# SimpleBattCharger.net
KiCad netlist of a schematic drawn in EAGLE
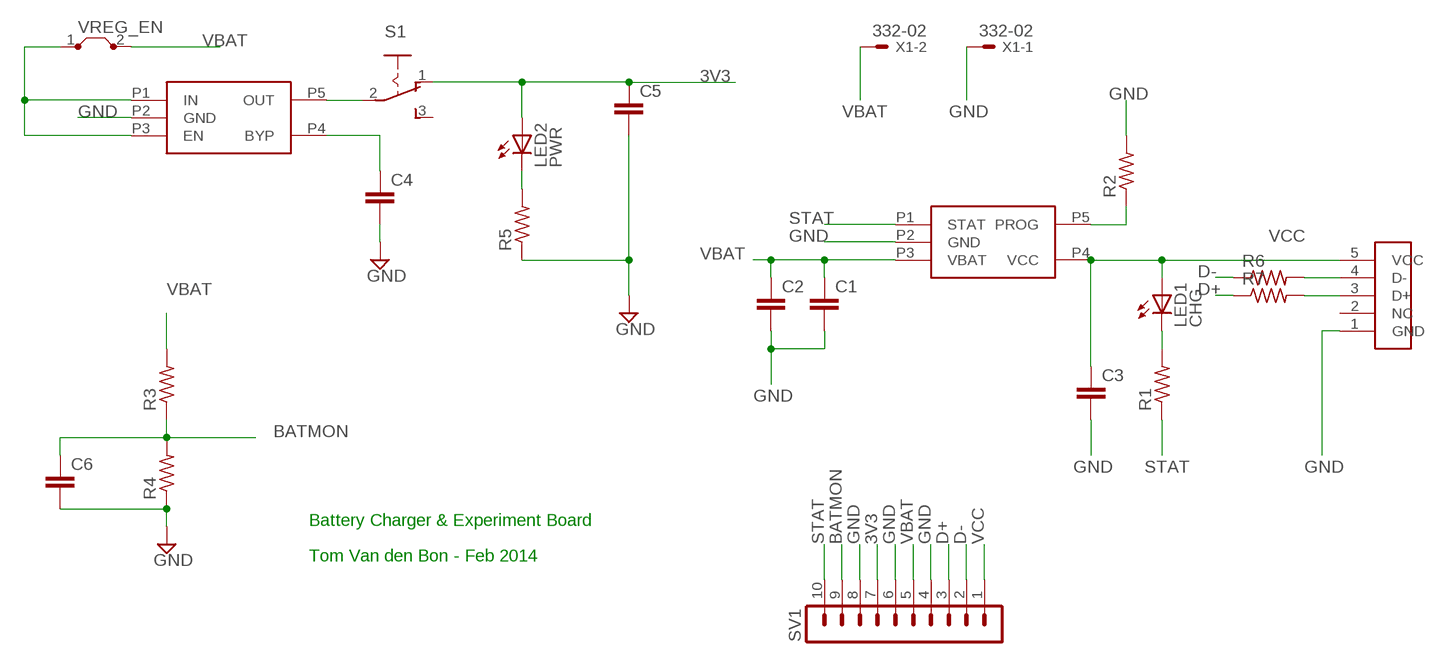
[diagram p0: schematic, sheet 1]

(export (version "E")
  (design (tool "Eeschema 10.0.6"))
  (components
    (comp (ref "C1")
      (value "C-EUC0603K")
      (footprint "eagle-import:C0603K")
      (libsource (lib "eagle-import") (part "C-EUC0603K"))
    )
    (comp (ref "C2")
      (value "C-EUC0603K")
      (footprint "eagle-import:C0603K")
      (libsource (lib "eagle-import") (part "C-EUC0603K"))
    )
    (comp (ref "C3")
      (value "C-EUC0603K")
      (footprint "eagle-import:C0603K")
      (libsource (lib "eagle-import") (part "C-EUC0603K"))
    )
    (comp (ref "C4")
      (value "C-EUC0603")
      (footprint "eagle-import:C0603")
      (libsource (lib "eagle-import") (part "C-EUC0603"))
    )
    (comp (ref "C5")
      (value "C-EUC3225")
      (footprint "eagle-import:C3225")
      (libsource (lib "eagle-import") (part "C-EUC3225"))
    )
    (comp (ref "C6")
      (value "C-EUC0603")
      (footprint "eagle-import:C0603")
      (libsource (lib "eagle-import") (part "C-EUC0603"))
    )
    (comp (ref "LED1")
      (value "CHG")
      (footprint "eagle-import:SML0603")
      (libsource (lib "eagle-import") (part "LEDSML0603"))
    )
    (comp (ref "LED2")
      (value "PWR")
      (footprint "eagle-import:SML0603")
      (libsource (lib "eagle-import") (part "LEDSML0603"))
    )
    (comp (ref "R1")
      (value "R-US_R0603")
      (footprint "eagle-import:R0603")
      (libsource (lib "eagle-import") (part "resistor_R-US_R0603"))
    )
    (comp (ref "R2")
      (value "R-US_R0603")
      (footprint "eagle-import:R0603")
      (libsource (lib "eagle-import") (part "resistor_R-US_R0603"))
    )
    (comp (ref "R3")
      (value "R-US_R0603")
      (footprint "eagle-import:R0603")
      (libsource (lib "eagle-import") (part "R-US_R0603"))
    )
    (comp (ref "R4")
      (value "R-US_R0603")
      (footprint "eagle-import:R0603")
      (libsource (lib "eagle-import") (part "R-US_R0603"))
    )
    (comp (ref "R5")
      (value "R-US_R0603")
      (footprint "eagle-import:R0603")
      (libsource (lib "eagle-import") (part "resistor_R-US_R0603"))
    )
    (comp (ref "R6")
      (value "R-US_R0603")
      (footprint "eagle-import:R0603")
      (libsource (lib "eagle-import") (part "resistor_R-US_R0603"))
    )
    (comp (ref "R7")
      (value "R-US_R0603")
      (footprint "eagle-import:R0603")
      (libsource (lib "eagle-import") (part "resistor_R-US_R0603"))
    )
    (comp (ref "S1")
      (value "255SB")
      (footprint "eagle-import:255SB")
      (libsource (lib "eagle-import") (part "255SB"))
    )
    (comp (ref "SV1")
      (value "MA10-1")
      (footprint "eagle-import:MA10-1")
      (libsource (lib "eagle-import") (part "MA10-1"))
    )
    (comp (ref "U$1")
      (value "USBSOCK_MINI_SMD")
      (footprint "eagle-import:USBSOCK_MINI_SMD")
      (libsource (lib "eagle-import") (part "USBSOCK_MINI_SMD"))
    )
    (comp (ref "U$2")
      (value "MCP73831MCP73831T-2ACI/OT")
      (footprint "eagle-import:SOT-23-5")
      (libsource (lib "eagle-import") (part "MCP73831MCP73831T-2ACI/OT"))
    )
    (comp (ref "U$3")
      (value "MIC5219-X.XBM5MIC5219-3.3YM5TR")
      (footprint "eagle-import:SOT-23-5")
      (libsource (lib "eagle-import") (part "MIC5219-X.XBM5MIC5219-3.3YM5TR"))
    )
    (comp (ref "VREG_EN")
      (value "J5MM")
      (footprint "eagle-import:05")
      (libsource (lib "eagle-import") (part "J5MM"))
    )
    (comp (ref "X1")
      (value "332-02")
      (footprint "eagle-import:332-02")
      (libsource (lib "eagle-import") (part "332-02"))
    )
  )
  (nets
    (net (code "1") (name "/3V3") (class "Default")
      (node (ref "C5") (pin "1") (pinfunction "1_1") (pintype "passive"))
      (node (ref "LED2") (pin "A") (pinfunction "A_A") (pintype "passive"))
      (node (ref "S1") (pin "1") (pinfunction "O_1") (pintype "passive"))
      (node (ref "SV1") (pin "7") (pinfunction "7_7") (pintype "passive"))
    )
    (net (code "2") (name "/BATMON") (class "Default")
      (node (ref "C6") (pin "1") (pinfunction "1_1") (pintype "passive"))
      (node (ref "R3") (pin "1") (pinfunction "1_1") (pintype "passive"))
      (node (ref "R4") (pin "2") (pinfunction "2_2") (pintype "passive"))
      (node (ref "SV1") (pin "9") (pinfunction "9_9") (pintype "passive"))
    )
    (net (code "3") (name "/D+") (class "Default")
      (node (ref "R7") (pin "1") (pinfunction "1_1") (pintype "passive"))
      (node (ref "SV1") (pin "3") (pinfunction "3_3") (pintype "passive"))
    )
    (net (code "4") (name "/D-") (class "Default")
      (node (ref "R6") (pin "1") (pinfunction "1_1") (pintype "passive"))
      (node (ref "SV1") (pin "2") (pinfunction "2_2") (pintype "passive"))
    )
    (net (code "5") (name "/STAT") (class "Default")
      (node (ref "R1") (pin "1") (pinfunction "1_1") (pintype "passive"))
      (node (ref "SV1") (pin "10") (pinfunction "10_10") (pintype "passive"))
      (node (ref "U$2") (pin "P1") (pinfunction "STAT_P1") (pintype "bidirectional"))
    )
    (net (code "6") (name "/VBAT") (class "Default")
      (node (ref "C1") (pin "1") (pinfunction "1_1") (pintype "passive"))
      (node (ref "C2") (pin "1") (pinfunction "1_1") (pintype "passive"))
      (node (ref "R3") (pin "2") (pinfunction "2_2") (pintype "passive"))
      (node (ref "SV1") (pin "5") (pinfunction "5_5") (pintype "passive"))
      (node (ref "U$2") (pin "P3") (pinfunction "VBAT_P3") (pintype "bidirectional"))
      (node (ref "VREG_EN") (pin "2") (pinfunction "2_2") (pintype "passive"))
      (node (ref "X1") (pin "2") (pinfunction "S_2") (pintype "passive"))
    )
    (net (code "7") (name "/VCC") (class "Default")
      (node (ref "C3") (pin "1") (pinfunction "1_1") (pintype "passive"))
      (node (ref "LED1") (pin "A") (pinfunction "A_A") (pintype "passive"))
      (node (ref "SV1") (pin "1") (pinfunction "1_1") (pintype "passive"))
      (node (ref "U$1") (pin "5") (pinfunction "VCC_5") (pintype "bidirectional"))
      (node (ref "U$2") (pin "P4") (pinfunction "VCC_P4") (pintype "bidirectional"))
    )
    (net (code "8") (name "GND") (class "Default")
      (node (ref "C1") (pin "2") (pinfunction "2_2") (pintype "passive"))
      (node (ref "C2") (pin "2") (pinfunction "2_2") (pintype "passive"))
      (node (ref "C3") (pin "2") (pinfunction "2_2") (pintype "passive"))
      (node (ref "C4") (pin "2") (pinfunction "2_2") (pintype "passive"))
      (node (ref "C5") (pin "2") (pinfunction "2_2") (pintype "passive"))
      (node (ref "C6") (pin "2") (pinfunction "2_2") (pintype "passive"))
      (node (ref "R2") (pin "2") (pinfunction "2_2") (pintype "passive"))
      (node (ref "R4") (pin "1") (pinfunction "1_1") (pintype "passive"))
      (node (ref "R5") (pin "1") (pinfunction "1_1") (pintype "passive"))
      (node (ref "SV1") (pin "4") (pinfunction "4_4") (pintype "passive"))
      (node (ref "SV1") (pin "6") (pinfunction "6_6") (pintype "passive"))
      (node (ref "SV1") (pin "8") (pinfunction "8_8") (pintype "passive"))
      (node (ref "U$1") (pin "1") (pinfunction "GND_1") (pintype "bidirectional"))
      (node (ref "U$2") (pin "P2") (pinfunction "GND_P2") (pintype "bidirectional"))
      (node (ref "U$3") (pin "P2") (pinfunction "GND_P2") (pintype "bidirectional"))
      (node (ref "X1") (pin "1") (pinfunction "S_1") (pintype "passive"))
    )
    (net (code "9") (name "Net-(LED1-PadC)") (class "Default")
      (node (ref "LED1") (pin "C") (pinfunction "C_C") (pintype "passive"))
      (node (ref "R1") (pin "2") (pinfunction "2_2") (pintype "passive"))
    )
    (net (code "10") (name "Net-(LED2-PadC)") (class "Default")
      (node (ref "LED2") (pin "C") (pinfunction "C_C") (pintype "passive"))
      (node (ref "R5") (pin "2") (pinfunction "2_2") (pintype "passive"))
    )
    (net (code "11") (name "Net-(S1-P)") (class "Default")
      (node (ref "S1") (pin "2") (pinfunction "P_2") (pintype "passive"))
      (node (ref "U$3") (pin "P5") (pinfunction "OUT_P5") (pintype "bidirectional"))
    )
    (net (code "12") (name "Net-(U$1-D+)") (class "Default")
      (node (ref "R7") (pin "2") (pinfunction "2_2") (pintype "passive"))
      (node (ref "U$1") (pin "3") (pinfunction "D+_3") (pintype "bidirectional"))
    )
    (net (code "13") (name "Net-(U$1-D-)") (class "Default")
      (node (ref "R6") (pin "2") (pinfunction "2_2") (pintype "passive"))
      (node (ref "U$1") (pin "4") (pinfunction "D-_4") (pintype "bidirectional"))
    )
    (net (code "14") (name "Net-(U$2-PROG)") (class "Default")
      (node (ref "R2") (pin "1") (pinfunction "1_1") (pintype "passive"))
      (node (ref "U$2") (pin "P5") (pinfunction "PROG_P5") (pintype "bidirectional"))
    )
    (net (code "15") (name "Net-(U$3-BYP)") (class "Default")
      (node (ref "C4") (pin "1") (pinfunction "1_1") (pintype "passive"))
      (node (ref "U$3") (pin "P4") (pinfunction "BYP_P4") (pintype "bidirectional"))
    )
    (net (code "16") (name "Net-(U$3-EN)") (class "Default")
      (node (ref "U$3") (pin "P1") (pinfunction "IN_P1") (pintype "bidirectional"))
      (node (ref "U$3") (pin "P3") (pinfunction "EN_P3") (pintype "bidirectional"))
      (node (ref "VREG_EN") (pin "1") (pinfunction "1_1") (pintype "passive"))
    )
    (net (code "17") (name "unconnected-(S1-S-Pad3)") (class "Default")
      (node (ref "S1") (pin "3") (pinfunction "S_3") (pintype "passive"))
    )
    (net (code "18") (name "unconnected-(U$1-NC-Pad2)") (class "Default")
      (node (ref "U$1") (pin "2") (pinfunction "NC_2") (pintype "bidirectional"))
    )
  )
)
